# MotorMosfet.net
KiCad netlist of a schematic drawn in Altium Designer
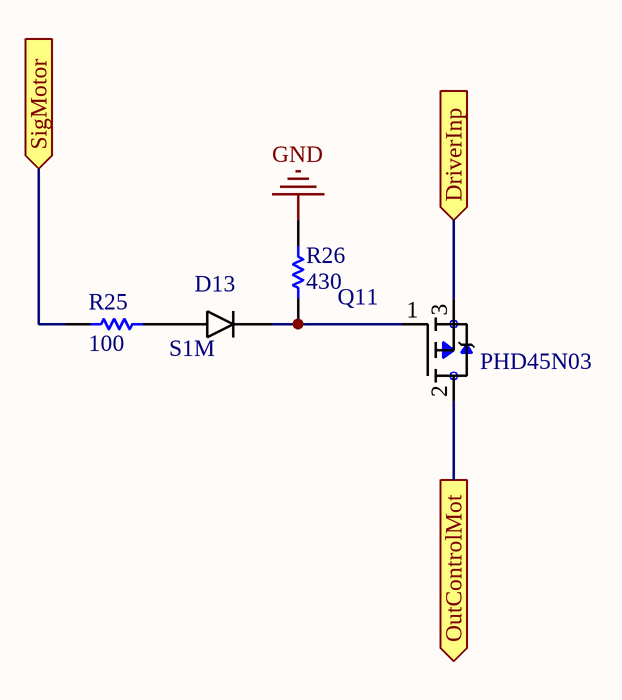
[diagram p0: MotorMosfet.SchDoc]

(export (version "E")
  (design (tool "Eeschema 10.0.6"))
  (components
    (comp (ref "D13")
      (value "S1M")
      (footprint "*DIOM5227X270N_S1M(Primary)")
      (description "S1 Series 1000 V 1 A 1 uA Surface Mount General Purpose Rectifier - DO-214AC")
      (fields (field (name "MF") "ON Semiconductor"))
      (libsource (lib "S1M") (part "S1M"))
    )
    (comp (ref "Q11")
      (value "PHD45N03")
      (footprint "*DPAK228P998X235-3N")
      (description "P-Channel 40 V 10.6 mOhm OptiMOSآ®-P2 Power-Transistor -PG-TO-252-3")
      (fields (field (name "MP") "IPD50P04P4L-11") (field (name "MF") "Infineon Technologies"))
      (libsource (lib "IPD50P04P4L-11") (part "IPD50P04P4L-11"))
    )
    (comp (ref "R25")
      (value "100")
      (footprint "6-0805_L")
      (description "Resistor")
      (fields (field (name "Comment") "R100") (field (name "PUBLISHER") "Altium Limited"))
      (libsource (lib "Miscellaneous Devices") (part "Res1"))
    )
    (comp (ref "R26")
      (value "430")
      (footprint "6-0805_L")
      (description "Resistor")
      (fields (field (name "Comment") "R430") (field (name "PUBLISHER") "Altium Limited"))
      (libsource (lib "Miscellaneous Devices") (part "Res1"))
    )
  )
  (nets
    (net (code "1") (name "/DriverInp") (class "Default")
      (node (ref "Q11") (pin "3") (pinfunction "S_3") (pintype "passive"))
    )
    (net (code "2") (name "/OutControlMot") (class "Default")
      (node (ref "Q11") (pin "2") (pinfunction "D_2") (pintype "passive"))
    )
    (net (code "3") (name "/SigMotor") (class "Default")
      (node (ref "R25") (pin "1") (pinfunction "1_1") (pintype "passive"))
    )
    (net (code "4") (name "GND") (class "Default")
      (node (ref "R26") (pin "1") (pinfunction "1_1") (pintype "passive"))
    )
    (net (code "5") (name "Net-(D13-K)") (class "Default")
      (node (ref "D13") (pin "C") (pinfunction "K_C") (pintype "passive"))
      (node (ref "Q11") (pin "1") (pinfunction "G_1") (pintype "passive"))
      (node (ref "R26") (pin "2") (pinfunction "2_2") (pintype "passive"))
    )
    (net (code "6") (name "Net-(D13-PadA)") (class "Default")
      (node (ref "D13") (pin "A") (pinfunction "A_A") (pintype "passive"))
      (node (ref "R25") (pin "2") (pinfunction "2_2") (pintype "passive"))
    )
  )
)
